# Gyroscope.net
KiCad netlist of a schematic drawn in Altium Designer
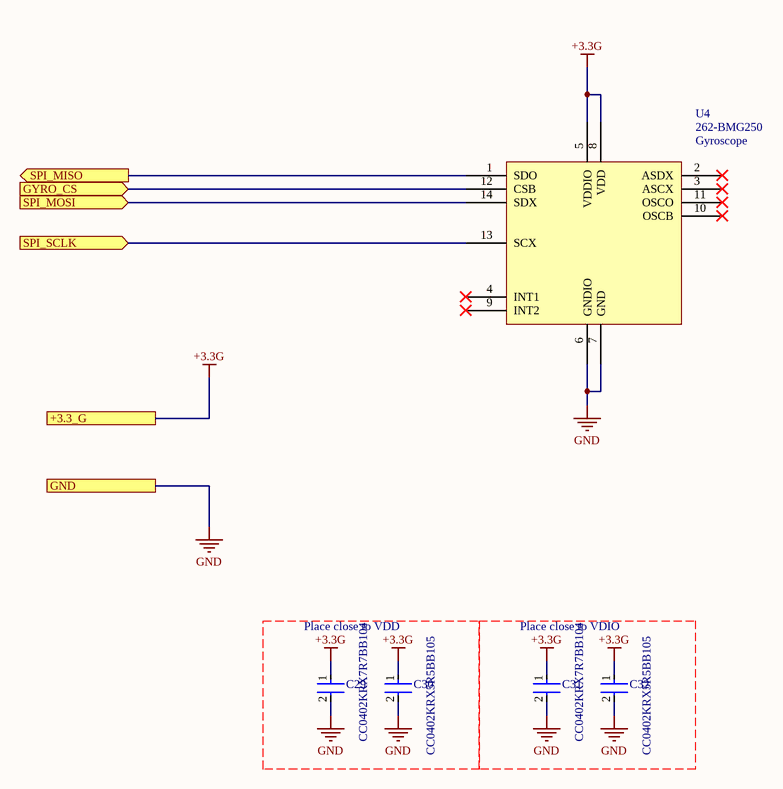
[diagram p0: Gyroscope.SchDoc]

(export (version "E")
  (design (tool "Eeschema 10.0.6"))
  (components
    (comp (ref "C29")
      (value "CC0402KRX7R7BB104")
      (footprint "FP-CC0402-MFG")
      (description "CAP CER 0.1UF 16V X7R 0402")
      (fields (field (name "MANUFACTURER") "YAGEO") (field (name "TOLERANCE") "0.1"))
      (libsource (lib "Altium Content Vault") (part "11868f565c42a9108669ba33697ecf6"))
    )
    (comp (ref "C30")
      (value "CC0402KRX5R5BB105")
      (footprint "FP-CC0402-MFG")
      (description "CAP CER 1UF 6.3V X5R 0402")
      (fields
        (field (name "MANUFACTURER") "YAGEO")
        (field (name "OCTOPART") "https://octopart.com/cc0402krx5r5bb105-yageo-42244618")
      )
      (libsource (lib "Altium Content Vault") (part "11868f565c42a9108669ba33697ecf6"))
    )
    (comp (ref "C31")
      (value "CC0402KRX7R7BB104")
      (footprint "FP-CC0402-MFG")
      (description "CAP CER 0.1UF 16V X7R 0402")
      (fields (field (name "MANUFACTURER") "YAGEO") (field (name "TOLERANCE") "0.1"))
      (libsource (lib "Altium Content Vault") (part "11868f565c42a9108669ba33697ecf6"))
    )
    (comp (ref "C32")
      (value "CC0402KRX5R5BB105")
      (footprint "FP-CC0402-MFG")
      (description "CAP CER 1UF 6.3V X5R 0402")
      (fields
        (field (name "MANUFACTURER") "YAGEO")
        (field (name "OCTOPART") "https://octopart.com/cc0402krx5r5bb105-yageo-42244618")
      )
      (libsource (lib "Altium Content Vault") (part "11868f565c42a9108669ba33697ecf6"))
    )
    (comp (ref "U4")
      (value "Gyroscope")
      (footprint "LGA14")
      (fields (field (name "SUPPLIER PART NUMBER 1") "262-BMG250"))
      (libsource (lib "Coin_lib") (part "BMG250"))
    )
  )
  (nets
    (net (code "1") (name "+3.3G") (class "Default")
      (node (ref "C29") (pin "1") (pinfunction "1_1") (pintype "passive"))
      (node (ref "C30") (pin "1") (pinfunction "1_1") (pintype "passive"))
      (node (ref "C31") (pin "1") (pinfunction "1_1") (pintype "passive"))
      (node (ref "C32") (pin "1") (pinfunction "1_1") (pintype "passive"))
      (node (ref "U4") (pin "5") (pinfunction "VDDIO_5") (pintype "passive"))
      (node (ref "U4") (pin "8") (pinfunction "VDD_8") (pintype "passive"))
    )
    (net (code "2") (name "/GYRO_CS") (class "Default")
      (node (ref "U4") (pin "12") (pinfunction "CSB_12") (pintype "passive"))
    )
    (net (code "3") (name "/SPI_MISO") (class "Default")
      (node (ref "U4") (pin "1") (pinfunction "SDO_1") (pintype "passive"))
    )
    (net (code "4") (name "/SPI_MOSI") (class "Default")
      (node (ref "U4") (pin "14") (pinfunction "SDX_14") (pintype "passive"))
    )
    (net (code "5") (name "/SPI_SCLK") (class "Default")
      (node (ref "U4") (pin "13") (pinfunction "SCX_13") (pintype "passive"))
    )
    (net (code "6") (name "GND") (class "Default")
      (node (ref "C29") (pin "2") (pinfunction "2_2") (pintype "passive"))
      (node (ref "C30") (pin "2") (pinfunction "2_2") (pintype "passive"))
      (node (ref "C31") (pin "2") (pinfunction "2_2") (pintype "passive"))
      (node (ref "C32") (pin "2") (pinfunction "2_2") (pintype "passive"))
      (node (ref "U4") (pin "6") (pinfunction "GNDIO_6") (pintype "passive"))
      (node (ref "U4") (pin "7") (pinfunction "GND_7") (pintype "passive"))
    )
    (net (code "7") (name "unconnected-(U4-ASCX-Pad3)") (class "Default")
      (node (ref "U4") (pin "3") (pinfunction "ASCX_3") (pintype "passive+no_connect"))
    )
    (net (code "8") (name "unconnected-(U4-ASDX-Pad2)") (class "Default")
      (node (ref "U4") (pin "2") (pinfunction "ASDX_2") (pintype "passive+no_connect"))
    )
    (net (code "9") (name "unconnected-(U4-INT1-Pad4)") (class "Default")
      (node (ref "U4") (pin "4") (pinfunction "INT1_4") (pintype "passive+no_connect"))
    )
    (net (code "10") (name "unconnected-(U4-INT2-Pad9)") (class "Default")
      (node (ref "U4") (pin "9") (pinfunction "INT2_9") (pintype "passive+no_connect"))
    )
    (net (code "11") (name "unconnected-(U4-OSCB-Pad10)") (class "Default")
      (node (ref "U4") (pin "10") (pinfunction "OSCB_10") (pintype "passive+no_connect"))
    )
    (net (code "12") (name "unconnected-(U4-OSCO-Pad11)") (class "Default")
      (node (ref "U4") (pin "11") (pinfunction "OSCO_11") (pintype "passive+no_connect"))
    )
  )
)
